# Circuito_Logico_NOT.net
KiCad netlist of a schematic drawn in EasyEDA Pro
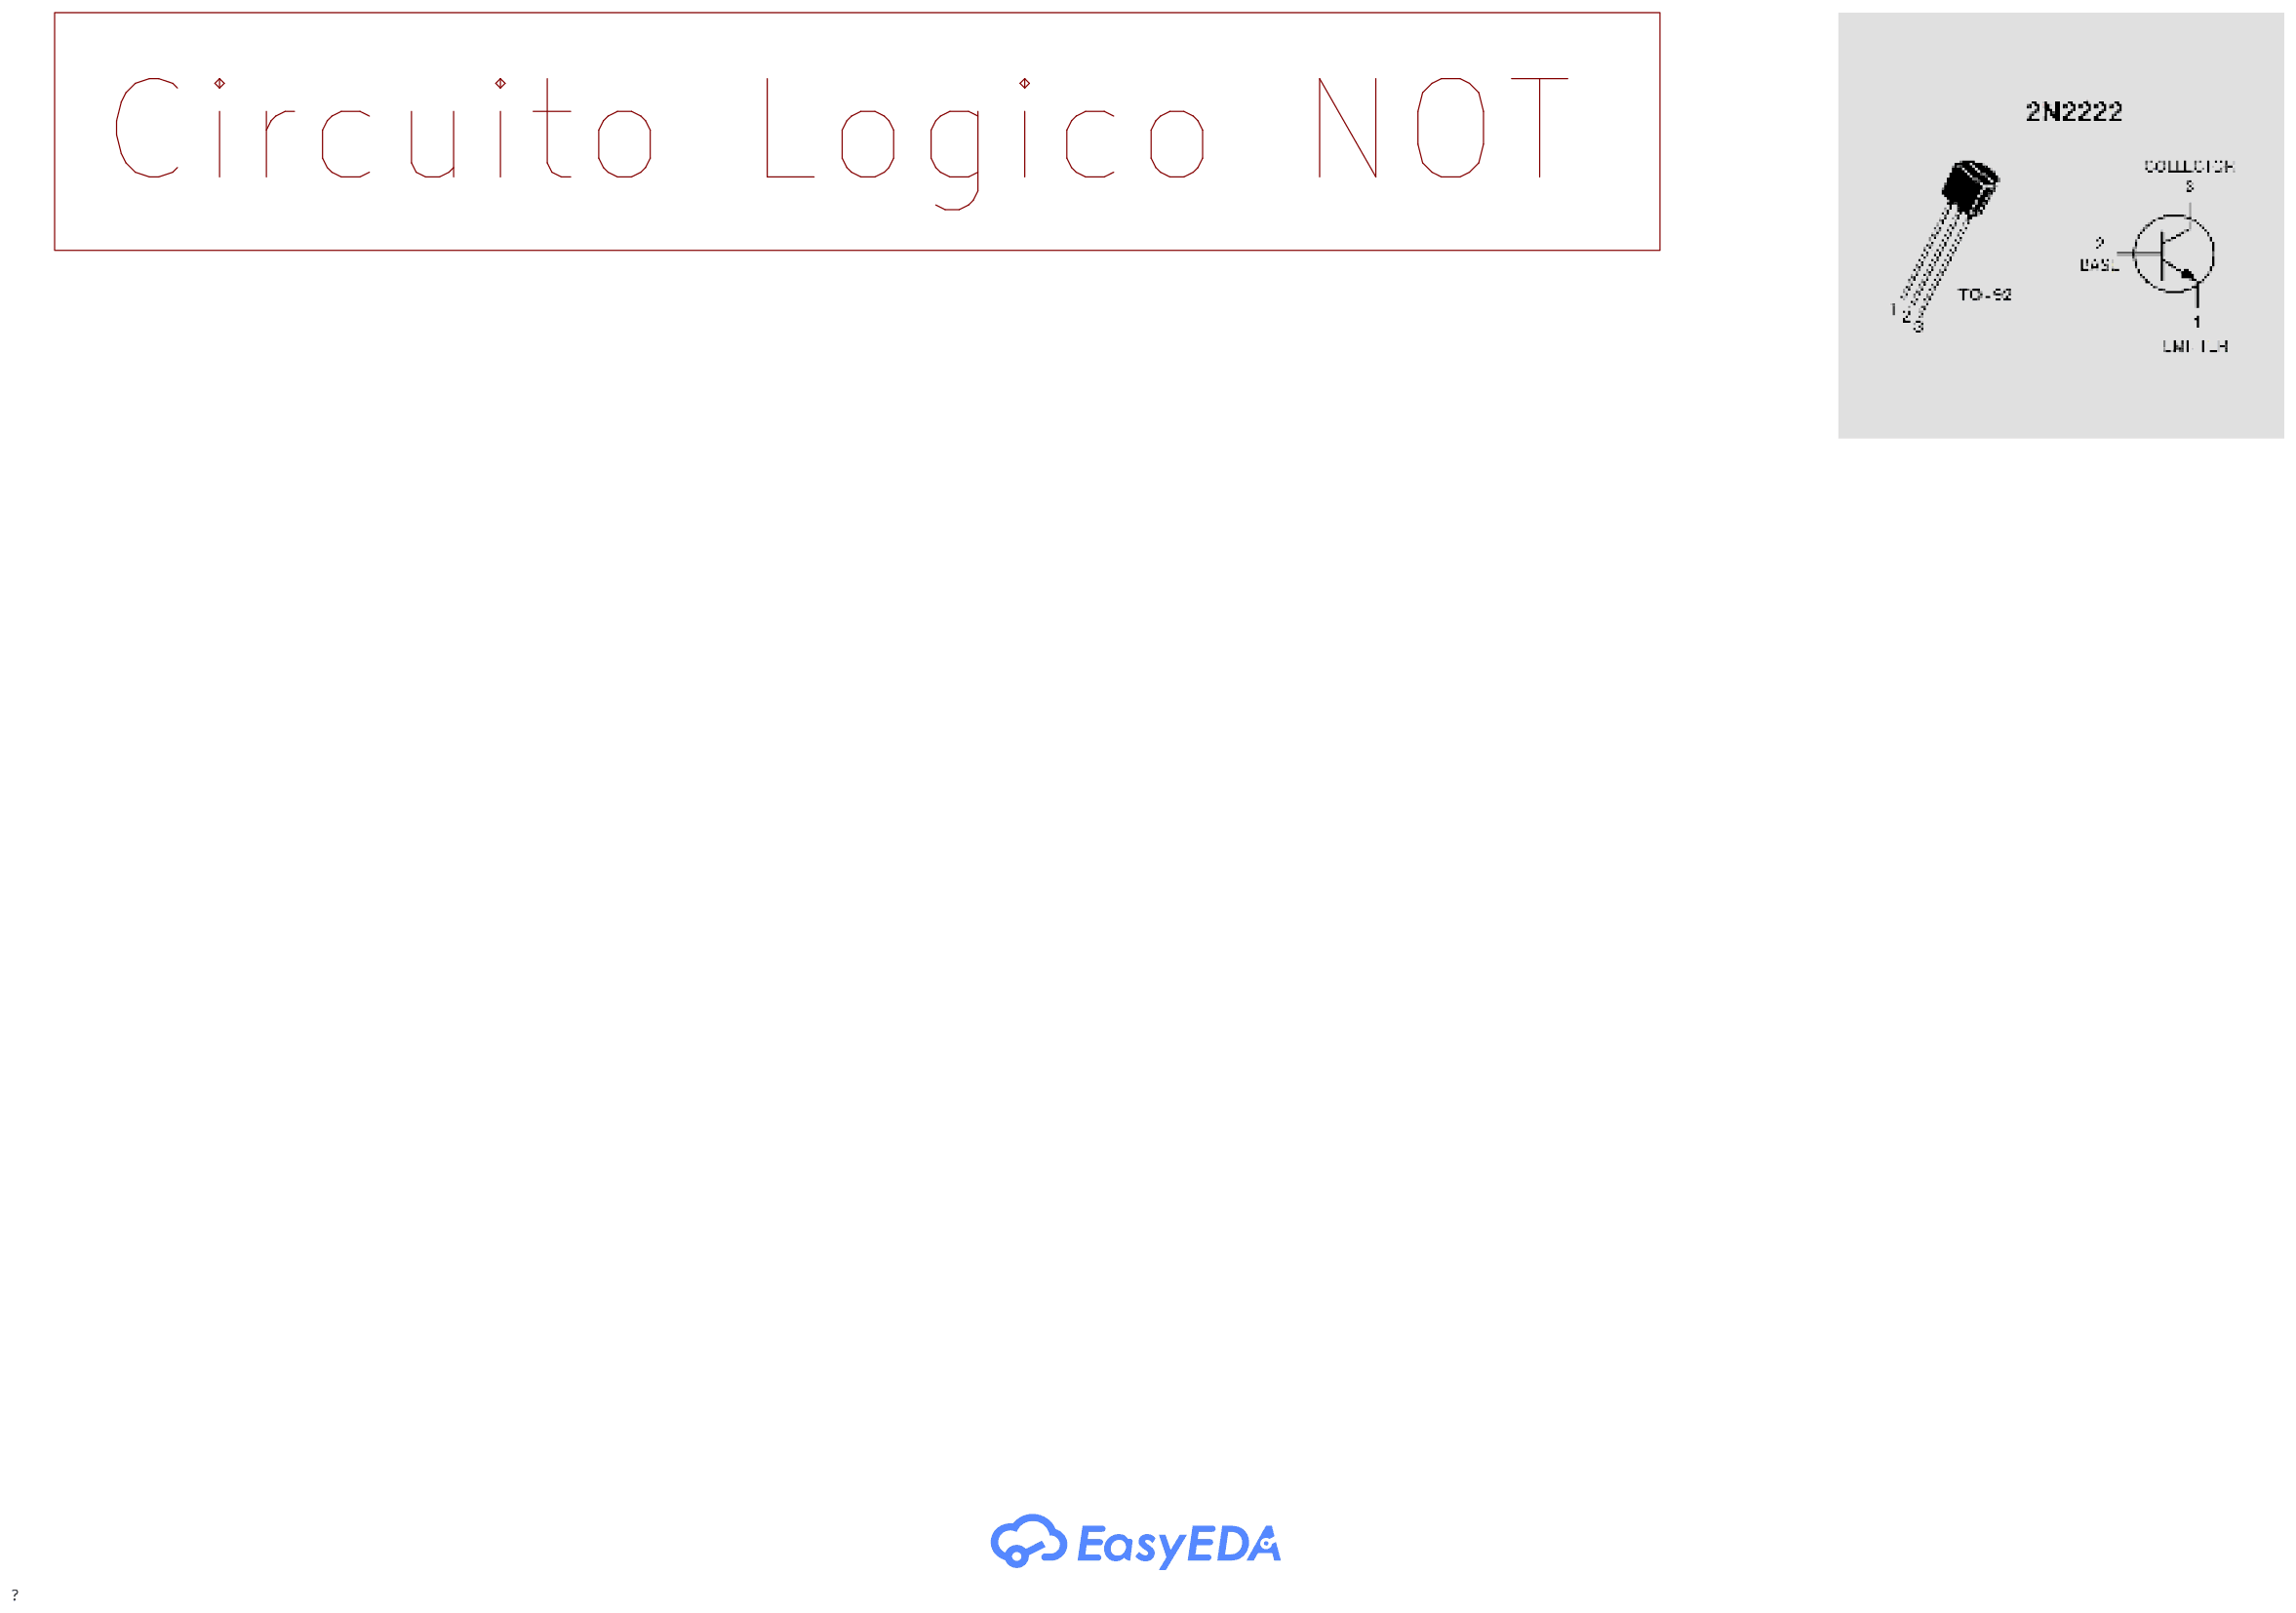
[diagram p0: P1]
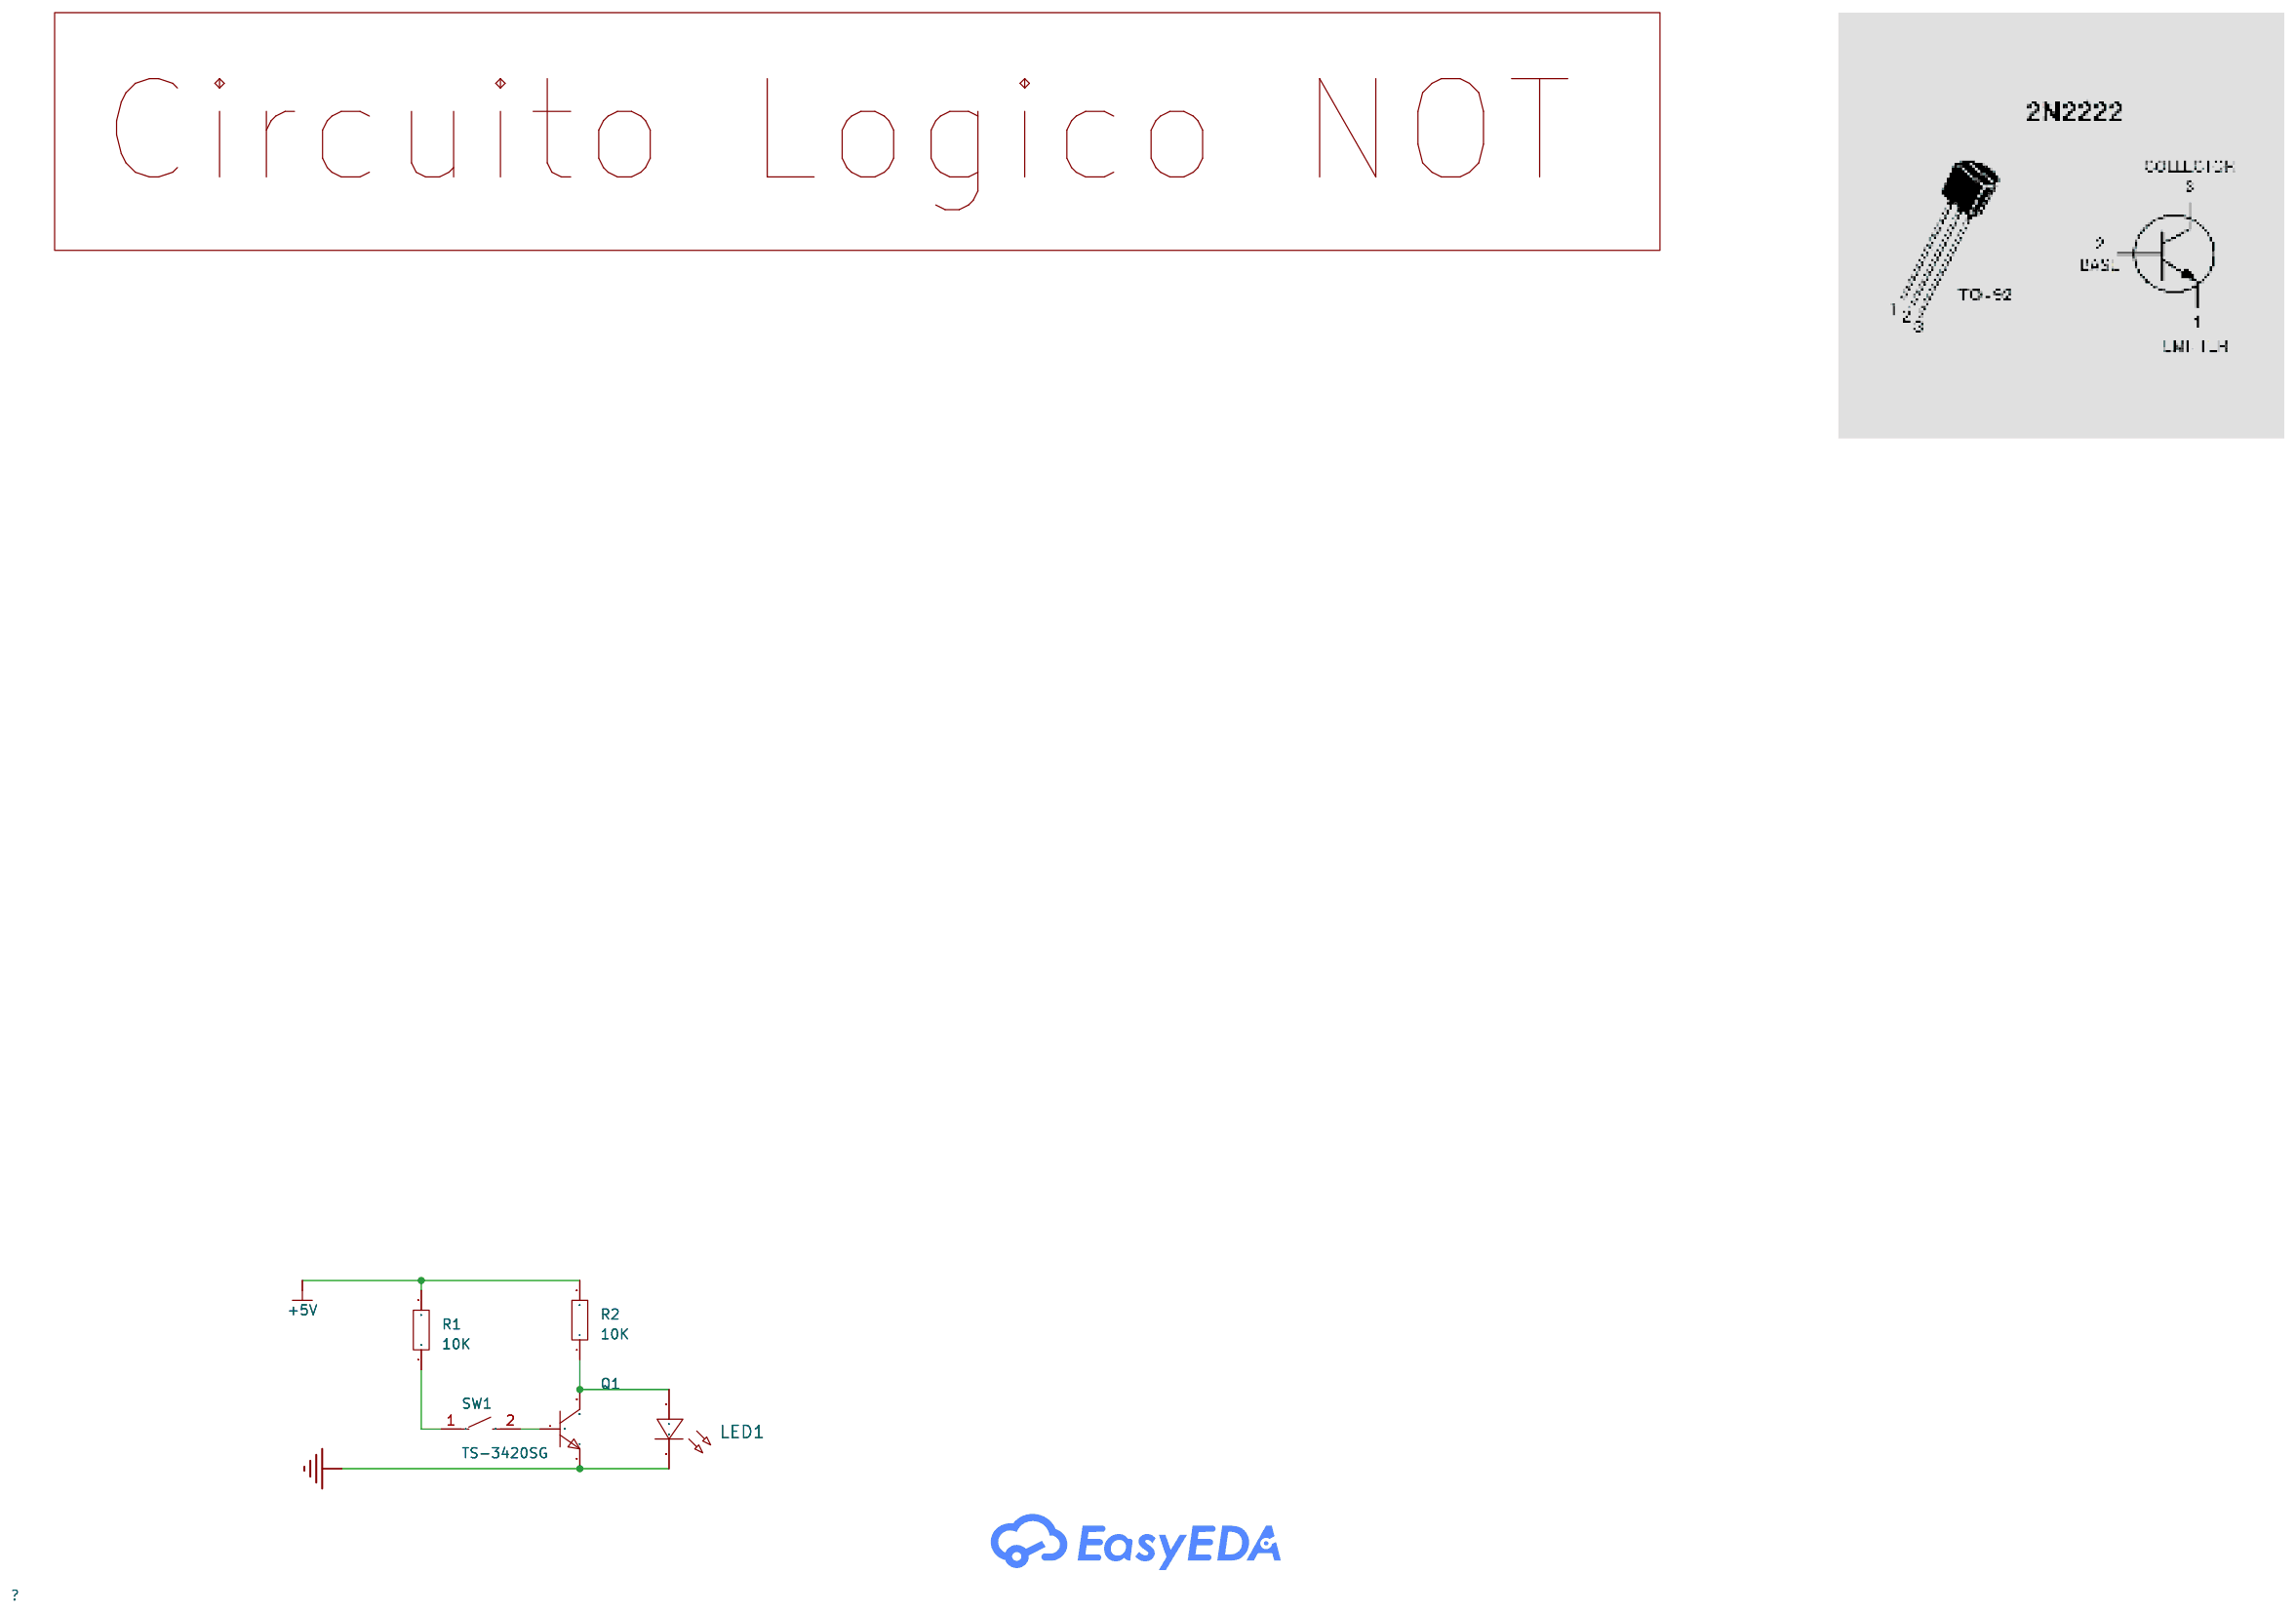
[diagram p1: P2]
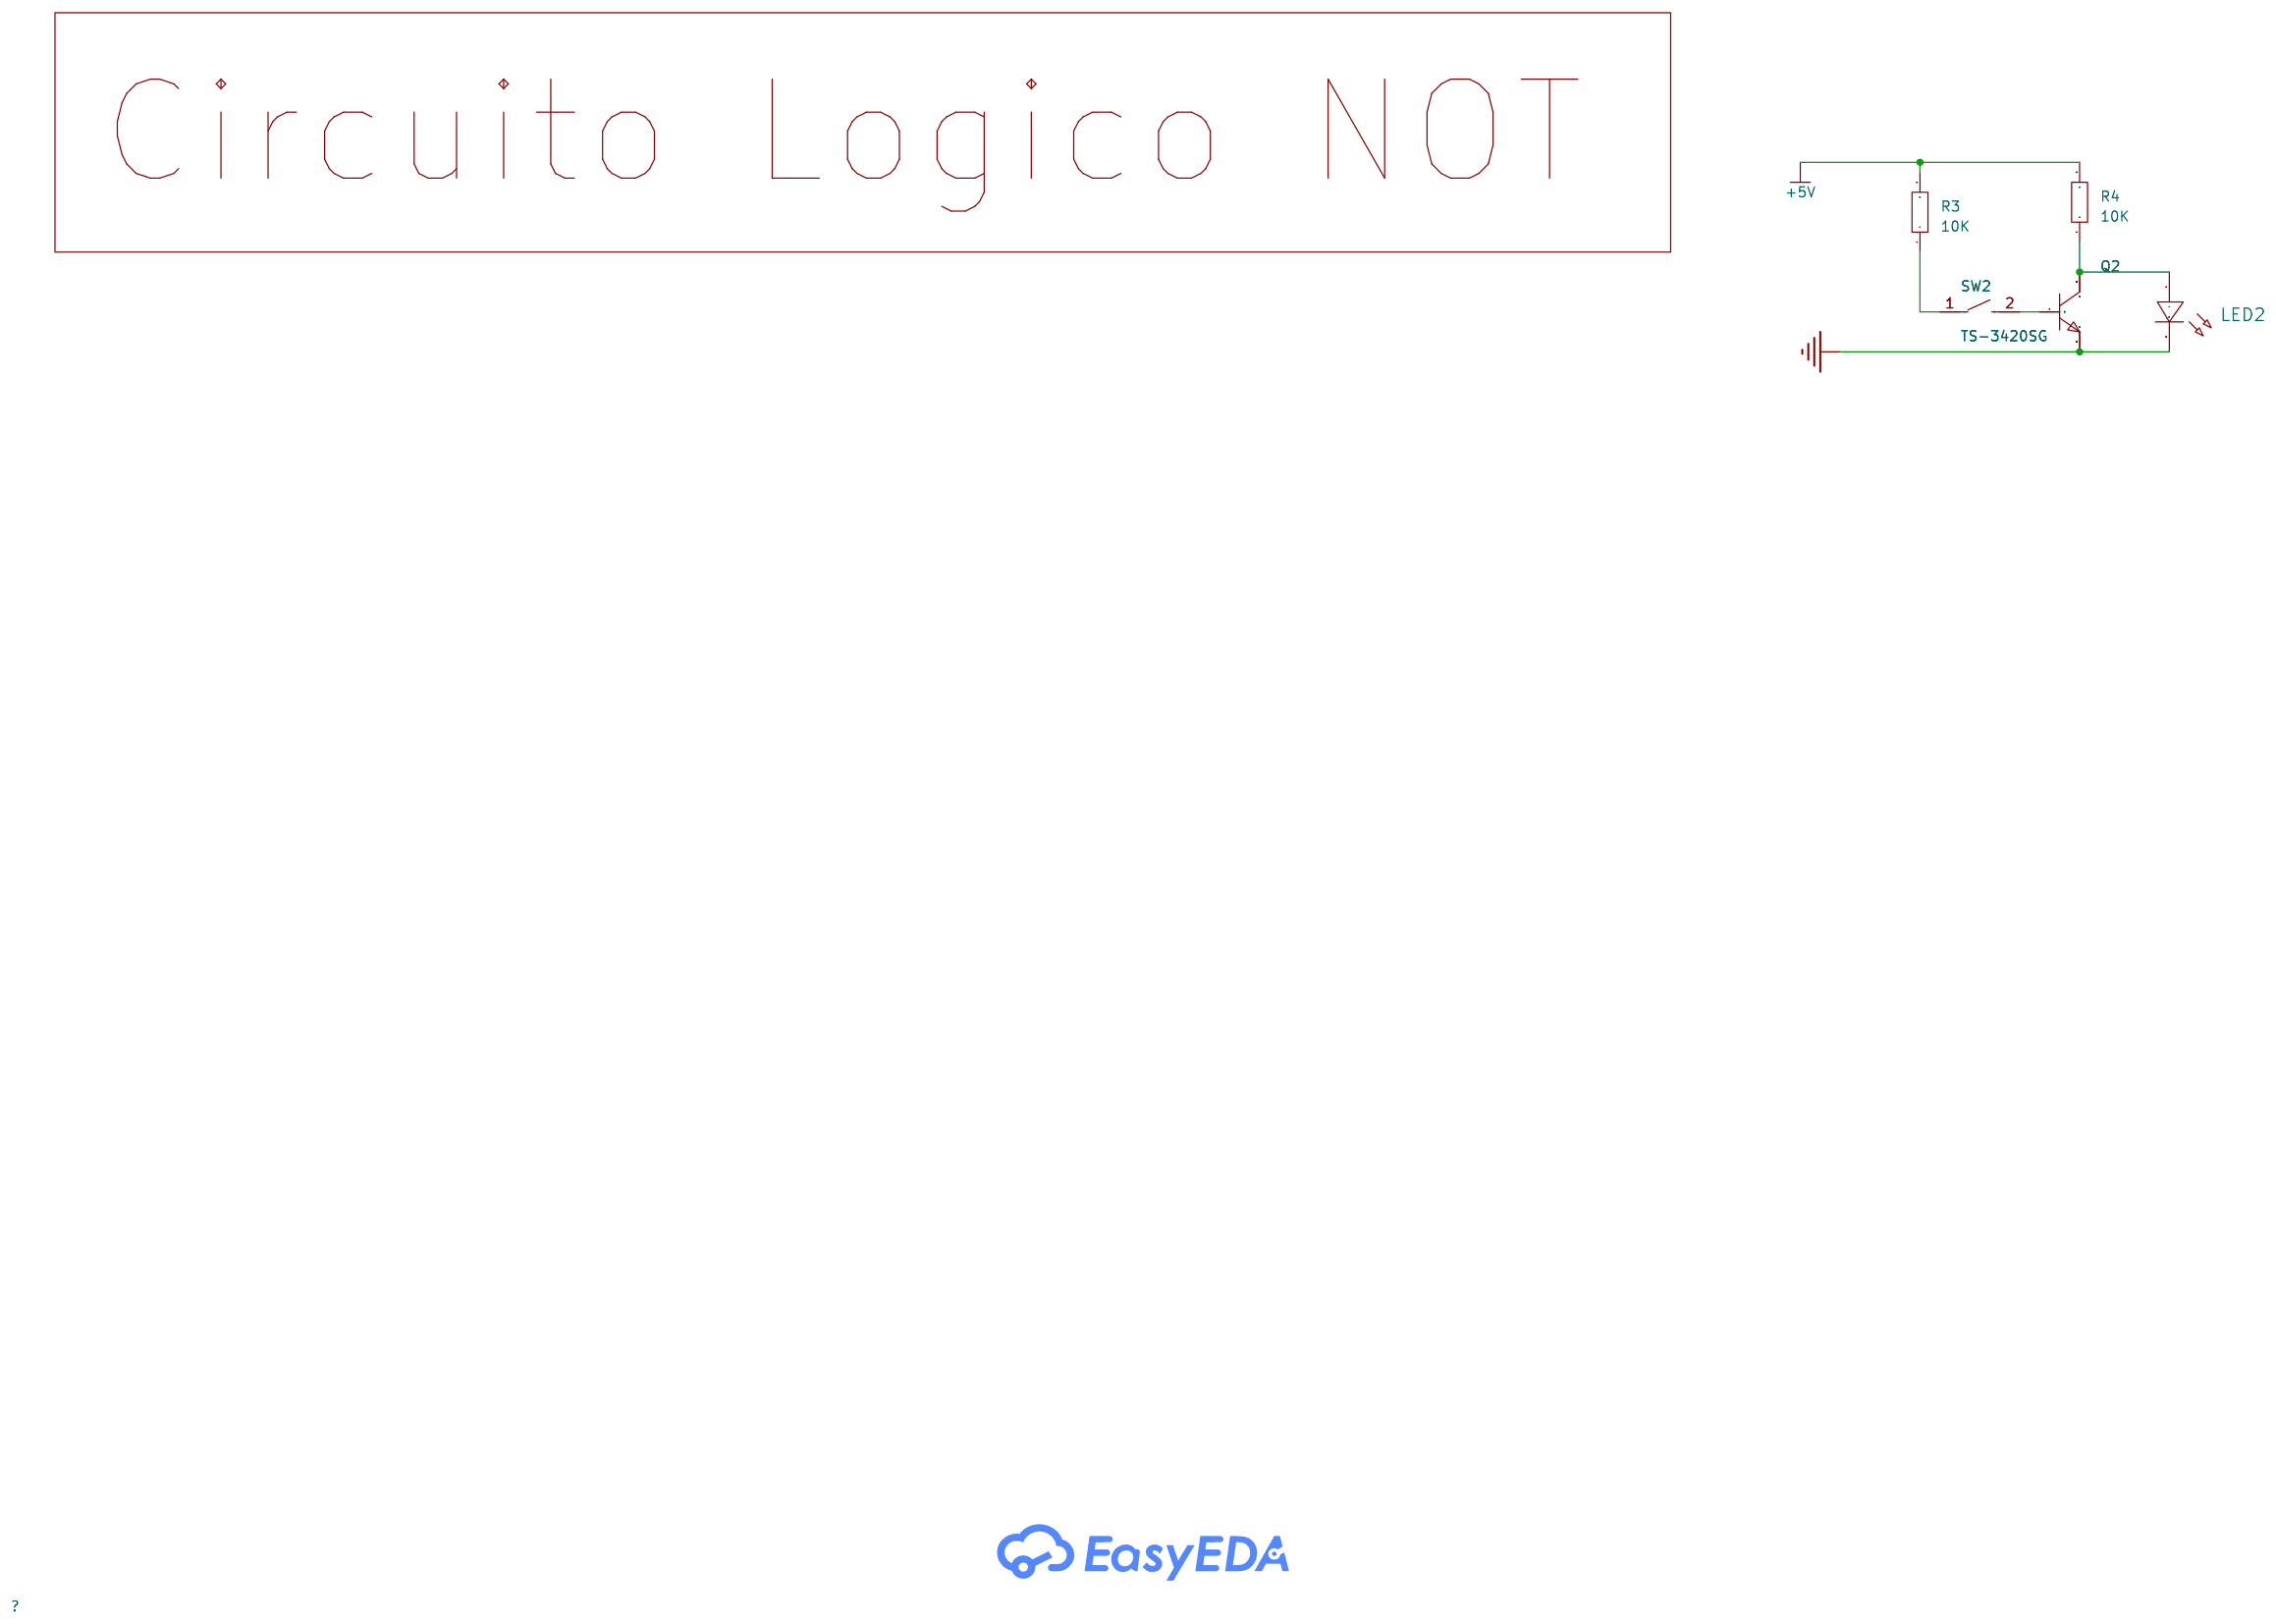
[diagram p2: P3]

(export (version "E")
  (design (tool "Eeschema 10.0.6"))
  (components
    (comp (ref "LED1")
      (value "~")
      (footprint "easyedapro:LED0402-RD_YELLOW")
      (libsource (lib "easyedapro") (part "LED_R"))
    )
    (comp (ref "Q1")
      (value "~")
      (footprint "easyedapro:TO-92-3_L4.9-W3.7-P1.27-L")
      (libsource (lib "easyedapro") (part "NPN"))
    )
    (comp (ref "R1") (value "10K") (footprint "easyedapro:R0603") (libsource (lib "easyedapro") (part "电阻")))
    (comp (ref "R2") (value "10K") (footprint "easyedapro:R0603") (libsource (lib "easyedapro") (part "电阻")))
    (comp (ref "SW1")
      (value "TS-3420SG")
      (footprint "easyedapro:SW-SMD_TS-3420SG")
      (fields (field (name "Manufacturer") "康深"))
      (libsource (lib "easyedapro") (part "TS-3420SG"))
    )
    (comp (ref "LED2")
      (value "~")
      (footprint "easyedapro:LED0402-RD_YELLOW")
      (libsource (lib "easyedapro") (part "LED_R"))
    )
    (comp (ref "Q2")
      (value "~")
      (footprint "easyedapro:TO-92-3_L4.9-W3.7-P1.27-L")
      (libsource (lib "easyedapro") (part "NPN"))
    )
    (comp (ref "R3") (value "10K") (footprint "easyedapro:R0603") (libsource (lib "easyedapro") (part "电阻")))
    (comp (ref "R4") (value "10K") (footprint "easyedapro:R0603") (libsource (lib "easyedapro") (part "电阻")))
    (comp (ref "SW2")
      (value "TS-3420SG")
      (footprint "easyedapro:SW-SMD_TS-3420SG")
      (fields (field (name "Manufacturer") "康深"))
      (libsource (lib "easyedapro") (part "TS-3420SG"))
    )
  )
  (nets
    (net (code "1") (name "+5V") (class "Default")
      (node (ref "R1") (pin "2") (pinfunction "2_2") (pintype "input"))
      (node (ref "R2") (pin "2") (pinfunction "2_2") (pintype "input"))
      (node (ref "R3") (pin "2") (pinfunction "2_2") (pintype "input"))
      (node (ref "R4") (pin "2") (pinfunction "2_2") (pintype "input"))
    )
    (net (code "2") (name "GND") (class "Default")
      (node (ref "LED1") (pin "2") (pinfunction "C_2") (pintype "input"))
      (node (ref "LED2") (pin "2") (pinfunction "C_2") (pintype "input"))
      (node (ref "Q1") (pin "2") (pinfunction "E_2") (pintype "unspecified"))
      (node (ref "Q2") (pin "2") (pinfunction "E_2") (pintype "unspecified"))
    )
    (net (code "3") (name "Net-(LED1-A)") (class "Default")
      (node (ref "LED1") (pin "1") (pinfunction "A_1") (pintype "input"))
      (node (ref "Q1") (pin "3") (pinfunction "C_3") (pintype "unspecified"))
      (node (ref "R2") (pin "1") (pinfunction "1_1") (pintype "input"))
    )
    (net (code "4") (name "Net-(LED2-A)") (class "Default")
      (node (ref "LED2") (pin "1") (pinfunction "A_1") (pintype "input"))
      (node (ref "Q2") (pin "3") (pinfunction "C_3") (pintype "unspecified"))
      (node (ref "R4") (pin "1") (pinfunction "1_1") (pintype "input"))
    )
    (net (code "5") (name "Net-(Q1-B)") (class "Default")
      (node (ref "Q1") (pin "1") (pinfunction "B_1") (pintype "unspecified"))
      (node (ref "SW1") (pin "2") (pinfunction "2_2") (pintype "unspecified"))
    )
    (net (code "6") (name "Net-(Q2-B)") (class "Default")
      (node (ref "Q2") (pin "1") (pinfunction "B_1") (pintype "unspecified"))
      (node (ref "SW2") (pin "2") (pinfunction "2_2") (pintype "unspecified"))
    )
    (net (code "7") (name "Net-(R1-Pad1)") (class "Default")
      (node (ref "R1") (pin "1") (pinfunction "1_1") (pintype "input"))
      (node (ref "SW1") (pin "1") (pinfunction "1_1") (pintype "unspecified"))
    )
    (net (code "8") (name "Net-(R3-Pad1)") (class "Default")
      (node (ref "R3") (pin "1") (pinfunction "1_1") (pintype "input"))
      (node (ref "SW2") (pin "1") (pinfunction "1_1") (pintype "unspecified"))
    )
  )
)
